# cheese_cave.net
KiCad netlist of a schematic drawn in Altium Designer
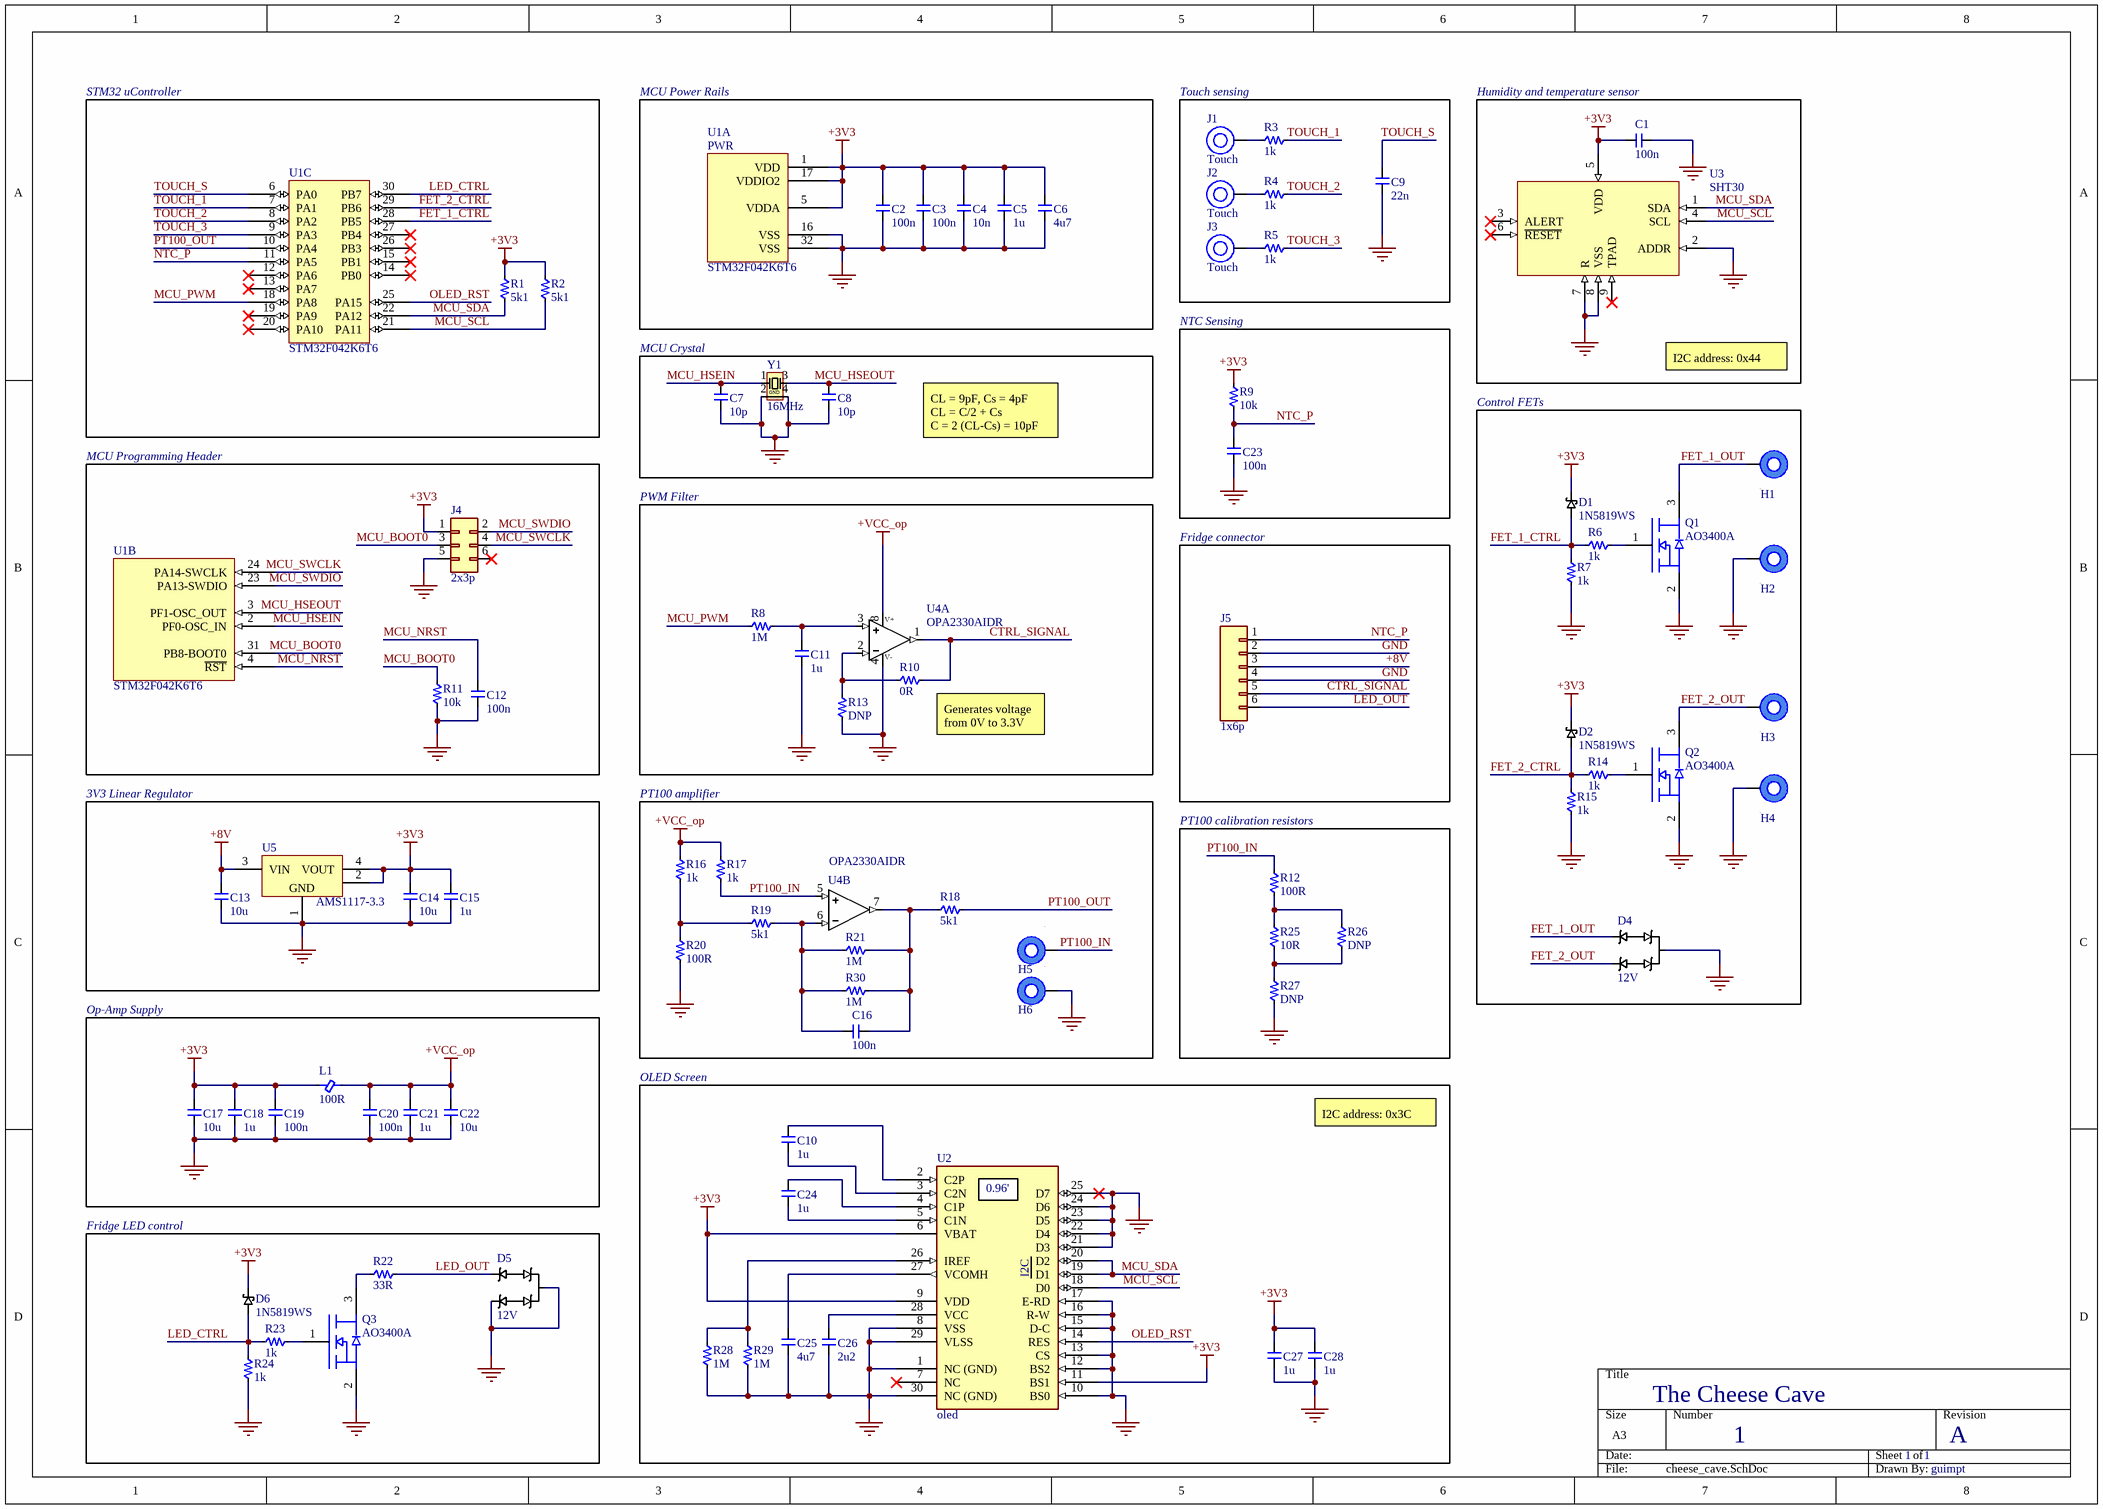
[diagram p0: cheese_cave.SchDoc]

(export (version "E")
  (design (tool "Eeschema 10.0.6"))
  (components
    (comp (ref "C1")
      (value "100n")
      (footprint "C0402")
      (description "0402 cap")
      (libsource (lib "FOC_Drive") (part "C_0402"))
    )
    (comp (ref "C2")
      (value "100n")
      (footprint "C0402")
      (description "0402 cap")
      (libsource (lib "FOC_Drive") (part "C_0402"))
    )
    (comp (ref "C3")
      (value "100n")
      (footprint "C0402")
      (description "0402 cap")
      (libsource (lib "FOC_Drive") (part "C_0402"))
    )
    (comp (ref "C4")
      (value "10n")
      (footprint "C0402")
      (description "0402 cap")
      (libsource (lib "cheese_cave") (part "C_0402"))
    )
    (comp (ref "C5")
      (value "1u")
      (footprint "C0805")
      (description "0805 cap")
      (libsource (lib "cheese_cave") (part "C_0805"))
    )
    (comp (ref "C6")
      (value "4u7")
      (footprint "C0805")
      (description "0805 cap")
      (libsource (lib "cheese_cave") (part "C_0805"))
    )
    (comp (ref "C7")
      (value "10p")
      (footprint "C0402")
      (description "0402 cap")
      (libsource (lib "FOC_Drive") (part "C_0402"))
    )
    (comp (ref "C8")
      (value "10p")
      (footprint "C0402")
      (description "0402 cap")
      (libsource (lib "FOC_Drive") (part "C_0402"))
    )
    (comp (ref "C9")
      (value "22n")
      (footprint "C0402")
      (description "0402 cap")
      (libsource (lib "FOC_Drive") (part "C_0402"))
    )
    (comp (ref "C10")
      (value "1u")
      (footprint "C0805")
      (description "0805 cap")
      (libsource (lib "cheese_cave") (part "C_0805"))
    )
    (comp (ref "C11")
      (value "1u")
      (footprint "C0805")
      (description "0805 cap")
      (libsource (lib "cheese_cave") (part "C_0805"))
    )
    (comp (ref "C12")
      (value "100n")
      (footprint "C0402")
      (description "0402 cap")
      (libsource (lib "FOC_Drive") (part "C_0402"))
    )
    (comp (ref "C13")
      (value "10u")
      (footprint "C0805")
      (description "0805 cap")
      (libsource (lib "FOC_Drive") (part "C_0805"))
    )
    (comp (ref "C14")
      (value "10u")
      (footprint "C0805")
      (description "0805 cap")
      (libsource (lib "FOC_Drive") (part "C_0805"))
    )
    (comp (ref "C15")
      (value "1u")
      (footprint "C0805")
      (description "0805 cap")
      (libsource (lib "cheese_cave") (part "C_0805"))
    )
    (comp (ref "C16")
      (value "100n")
      (footprint "C0402")
      (description "0402 cap")
      (libsource (lib "FOC_Drive") (part "C_0402"))
    )
    (comp (ref "C17")
      (value "10u")
      (footprint "C0805")
      (description "0805 cap")
      (libsource (lib "FOC_Drive") (part "C_0805"))
    )
    (comp (ref "C18")
      (value "1u")
      (footprint "C0805")
      (description "0805 cap")
      (libsource (lib "cheese_cave") (part "C_0805"))
    )
    (comp (ref "C19")
      (value "100n")
      (footprint "C0402")
      (description "0402 cap")
      (libsource (lib "FOC_Drive") (part "C_0402"))
    )
    (comp (ref "C20")
      (value "100n")
      (footprint "C0402")
      (description "0402 cap")
      (libsource (lib "FOC_Drive") (part "C_0402"))
    )
    (comp (ref "C21")
      (value "1u")
      (footprint "C0805")
      (description "0805 cap")
      (libsource (lib "cheese_cave") (part "C_0805"))
    )
    (comp (ref "C22")
      (value "10u")
      (footprint "C0805")
      (description "0805 cap")
      (libsource (lib "FOC_Drive") (part "C_0805"))
    )
    (comp (ref "C23")
      (value "100n")
      (footprint "C0402")
      (description "0402 cap")
      (libsource (lib "FOC_Drive") (part "C_0402"))
    )
    (comp (ref "C24")
      (value "1u")
      (footprint "C0805")
      (description "0805 cap")
      (libsource (lib "cheese_cave") (part "C_0805"))
    )
    (comp (ref "C25")
      (value "4u7")
      (footprint "C0805")
      (description "0805 cap")
      (libsource (lib "cheese_cave") (part "C_0805"))
    )
    (comp (ref "C26")
      (value "2u2")
      (footprint "C0805")
      (description "0805 cap")
      (libsource (lib "FOC_Drive") (part "C_0805"))
    )
    (comp (ref "C27")
      (value "1u")
      (footprint "C0805")
      (description "0805 cap")
      (libsource (lib "cheese_cave") (part "C_0805"))
    )
    (comp (ref "C28")
      (value "1u")
      (footprint "C0805")
      (description "0805 cap")
      (libsource (lib "cheese_cave") (part "C_0805"))
    )
    (comp (ref "D1")
      (value "1N5819WS")
      (footprint "SOD323")
      (description "40V 600mV@1A 1A SOD-323  Schottky")
      (libsource (lib "cheese_cave") (part "1N5819WS"))
    )
    (comp (ref "D2")
      (value "1N5819WS")
      (footprint "SOD323")
      (description "40V 600mV@1A 1A SOD-323  Schottky")
      (libsource (lib "cheese_cave") (part "1N5819WS"))
    )
    (comp (ref "D4")
      (value "12V")
      (footprint "SOT23_protek")
      (description "19V 13.3V 12V SOT-23(TO-236)  TVS")
      (libsource (lib "cheese_cave") (part "PSM712-LF-T7"))
    )
    (comp (ref "D5")
      (value "12V")
      (footprint "SOT23_protek")
      (description "19V 13.3V 12V SOT-23(TO-236)  TVS")
      (libsource (lib "cheese_cave") (part "PSM712-LF-T7"))
    )
    (comp (ref "D6")
      (value "1N5819WS")
      (footprint "SOD323")
      (description "40V 600mV@1A 1A SOD-323  Schottky")
      (libsource (lib "cheese_cave") (part "1N5819WS"))
    )
    (comp (ref "H1")
      (value "1x1")
      (footprint "1x1p")
      (description "0.85mm hole")
      (libsource (lib "cheese_cave") (part "1x1p"))
    )
    (comp (ref "H2")
      (value "1x1")
      (footprint "1x1p")
      (description "0.85mm hole")
      (libsource (lib "cheese_cave") (part "1x1p"))
    )
    (comp (ref "H3")
      (value "1x1")
      (footprint "1x1p")
      (description "0.85mm hole")
      (libsource (lib "cheese_cave") (part "1x1p"))
    )
    (comp (ref "H4")
      (value "1x1")
      (footprint "1x1p")
      (description "0.85mm hole")
      (libsource (lib "cheese_cave") (part "1x1p"))
    )
    (comp (ref "H5")
      (value "1x1")
      (footprint "1x1p")
      (description "0.85mm hole")
      (libsource (lib "cheese_cave") (part "1x1p"))
    )
    (comp (ref "H6")
      (value "1x1")
      (footprint "1x1p")
      (description "0.85mm hole")
      (libsource (lib "cheese_cave") (part "1x1p"))
    )
    (comp (ref "J1")
      (value "Touch")
      (footprint "F10-10-6.5-0.4 Z")
      (libsource (lib "cheese_cave") (part "F10-10-6.5-0.4Z"))
    )
    (comp (ref "J2")
      (value "Touch")
      (footprint "F10-10-6.5-0.4 Z")
      (libsource (lib "cheese_cave") (part "F10-10-6.5-0.4Z"))
    )
    (comp (ref "J3")
      (value "Touch")
      (footprint "F10-10-6.5-0.4 Z")
      (libsource (lib "cheese_cave") (part "F10-10-6.5-0.4Z"))
    )
    (comp (ref "J4")
      (value "2x3p")
      (footprint "2x3p_conn")
      (description "2x3 male pin header")
      (libsource (lib "FOC_Drive") (part "2x3p_conn"))
    )
    (comp (ref "J5")
      (value "1x6p")
      (footprint "1X6P_CONN")
      (description "1x6 male pin header")
      (libsource (lib "cheese_cave") (part "1x6p_conn"))
    )
    (comp (ref "L1")
      (value "100R")
      (footprint "L0805")
      (description "±25% 100Ω@100MHz 0805  150mR Ferrite Beads")
      (libsource (lib "cheese_cave") (part "GZ2012D101TF"))
    )
    (comp (ref "Q1")
      (value "AO3400A")
      (footprint "SOT23_alphaomega")
      (description "30V 5.7A 26.5mΩ@10V,5.7A 1.4W N Channel SOT-23-3L  MOSFET")
      (libsource (lib "cheese_cave") (part "AO3400A"))
    )
    (comp (ref "Q2")
      (value "AO3400A")
      (footprint "SOT23_alphaomega")
      (description "30V 5.7A 26.5mΩ@10V,5.7A 1.4W N Channel SOT-23-3L  MOSFET")
      (libsource (lib "cheese_cave") (part "AO3400A"))
    )
    (comp (ref "Q3")
      (value "AO3400A")
      (footprint "SOT23_alphaomega")
      (description "30V 5.7A 26.5mΩ@10V,5.7A 1.4W N Channel SOT-23-3L  MOSFET")
      (libsource (lib "cheese_cave") (part "AO3400A"))
    )
    (comp (ref "R1")
      (value "5k1")
      (footprint "R0402")
      (description "0402 62.5mW")
      (libsource (lib "FOC_Drive") (part "R_0402"))
    )
    (comp (ref "R2")
      (value "5k1")
      (footprint "R0402")
      (description "0402 62.5mW")
      (libsource (lib "FOC_Drive") (part "R_0402"))
    )
    (comp (ref "R3")
      (value "1k")
      (footprint "R0402")
      (description "0402 62.5mW")
      (libsource (lib "FOC_Drive") (part "R_0402"))
    )
    (comp (ref "R4")
      (value "1k")
      (footprint "R0402")
      (description "0402 62.5mW")
      (libsource (lib "FOC_Drive") (part "R_0402"))
    )
    (comp (ref "R5")
      (value "1k")
      (footprint "R0402")
      (description "0402 62.5mW")
      (libsource (lib "FOC_Drive") (part "R_0402"))
    )
    (comp (ref "R6")
      (value "1k")
      (footprint "R0402")
      (description "0402 62.5mW")
      (libsource (lib "FOC_Drive") (part "R_0402"))
    )
    (comp (ref "R7")
      (value "1k")
      (footprint "R0402")
      (description "0402 62.5mW")
      (libsource (lib "FOC_Drive") (part "R_0402"))
    )
    (comp (ref "R8")
      (value "1M")
      (footprint "R0402")
      (description "0402 62.5mW")
      (libsource (lib "FOC_Drive") (part "R_0402"))
    )
    (comp (ref "R9")
      (value "10k")
      (footprint "R0402")
      (description "0402 62.5mW")
      (libsource (lib "FOC_Drive") (part "R_0402"))
    )
    (comp (ref "R10")
      (value "0R")
      (footprint "R0402")
      (description "0402 62.5mW")
      (libsource (lib "FOC_Drive") (part "R_0402"))
    )
    (comp (ref "R11")
      (value "10k")
      (footprint "R0402")
      (description "0402 62.5mW")
      (libsource (lib "FOC_Drive") (part "R_0402"))
    )
    (comp (ref "R12")
      (value "100R")
      (footprint "R0402")
      (description "0402 62.5mW")
      (libsource (lib "FOC_Drive") (part "R_0402"))
    )
    (comp (ref "R13")
      (value "DNP")
      (footprint "R0402")
      (description "0402 62.5mW")
      (libsource (lib "FOC_Drive") (part "R_0402"))
    )
    (comp (ref "R14")
      (value "1k")
      (footprint "R0402")
      (description "0402 62.5mW")
      (libsource (lib "FOC_Drive") (part "R_0402"))
    )
    (comp (ref "R15")
      (value "1k")
      (footprint "R0402")
      (description "0402 62.5mW")
      (libsource (lib "FOC_Drive") (part "R_0402"))
    )
    (comp (ref "R16")
      (value "1k")
      (footprint "R0402")
      (description "0402 62.5mW")
      (libsource (lib "FOC_Drive") (part "R_0402"))
    )
    (comp (ref "R17")
      (value "1k")
      (footprint "R0402")
      (description "0402 62.5mW")
      (libsource (lib "FOC_Drive") (part "R_0402"))
    )
    (comp (ref "R18")
      (value "5k1")
      (footprint "R0402")
      (description "0402 62.5mW")
      (libsource (lib "FOC_Drive") (part "R_0402"))
    )
    (comp (ref "R19")
      (value "5k1")
      (footprint "R0402")
      (description "0402 62.5mW")
      (libsource (lib "FOC_Drive") (part "R_0402"))
    )
    (comp (ref "R20")
      (value "100R")
      (footprint "R0402")
      (description "0402 62.5mW")
      (libsource (lib "FOC_Drive") (part "R_0402"))
    )
    (comp (ref "R21")
      (value "1M")
      (footprint "R0402")
      (description "0402 62.5mW")
      (libsource (lib "FOC_Drive") (part "R_0402"))
    )
    (comp (ref "R22")
      (value "33R")
      (footprint "R0402")
      (description "0402 62.5mW")
      (libsource (lib "FOC_Drive") (part "R_0402"))
    )
    (comp (ref "R23")
      (value "1k")
      (footprint "R0402")
      (description "0402 62.5mW")
      (libsource (lib "FOC_Drive") (part "R_0402"))
    )
    (comp (ref "R24")
      (value "1k")
      (footprint "R0402")
      (description "0402 62.5mW")
      (libsource (lib "FOC_Drive") (part "R_0402"))
    )
    (comp (ref "R25")
      (value "10R")
      (footprint "R0402")
      (description "0402 62.5mW")
      (libsource (lib "FOC_Drive") (part "R_0402"))
    )
    (comp (ref "R26")
      (value "DNP")
      (footprint "R0402")
      (description "0402 62.5mW")
      (libsource (lib "FOC_Drive") (part "R_0402"))
    )
    (comp (ref "R27")
      (value "DNP")
      (footprint "R0402")
      (description "0402 62.5mW")
      (libsource (lib "FOC_Drive") (part "R_0402"))
    )
    (comp (ref "R28")
      (value "1M")
      (footprint "R0402")
      (description "0402 62.5mW")
      (libsource (lib "FOC_Drive") (part "R_0402"))
    )
    (comp (ref "R29")
      (value "1M")
      (footprint "R0402")
      (description "0402 62.5mW")
      (libsource (lib "FOC_Drive") (part "R_0402"))
    )
    (comp (ref "R30")
      (value "1M")
      (footprint "R0402")
      (description "0402 62.5mW")
      (libsource (lib "FOC_Drive") (part "R_0402"))
    )
    (comp (ref "U1")
      (value "STM32F042K6T6")
      (footprint "LQFP32-ST")
      (description "RISC Microcontroller, 32-Bit, FLASH, CORTEX-M0 CPU, 48MHz, CMOS, PQFP32")
      (fields (field (name "MANUFACTURER") "STMicroelectronics"))
      (libsource (lib "cheese_cave") (part "STM32F042K6T6"))
    )
    (comp (ref "U2")
      (value "oled")
      (footprint "OLED_096_SSD1306")
      (description "0.96 inch frameless SSD1306 oled")
      (libsource (lib "cheese_cave") (part "OLED_096_SSD1306"))
    )
    (comp (ref "U3")
      (value "SHT30")
      (footprint "SHT30-DIS-B2.5KS")
      (description "Temperature and Humidity Sensor")
      (libsource (lib "cheese_cave") (part "SHT30-DIS-B2.5KS"))
    )
    (comp (ref "U4")
      (value "OPA2330AIDR")
      (footprint "SOIC8")
      (description "Precision opamp")
      (libsource (lib "cheese_cave") (part "OPA2330AIDR"))
    )
    (comp (ref "U5")
      (value "AMS1117-3.3")
      (footprint "SOT223")
      (description "72dB@(120Hz) 1A 1.3V@(800mA) Fixed 3.3V~3.3V Positive 1 SOT-223")
      (libsource (lib "FOC_Drive") (part "AMS1117-3.3"))
    )
    (comp (ref "Y1")
      (value "16MHz")
      (footprint "SMD3225-4P")
      (description "16MHz SMD Crystal Resonator 9pF ±10ppm ±30ppm -40℃~+85℃ SMD3225-4P Crystals ROHS")
      (libsource (lib "FOC_Drive") (part "X322516MLB4SI"))
    )
  )
  (nets
    (net (code "1") (name "+3V3") (class "Default")
      (node (ref "C1") (pin "1") (pinfunction "1_1") (pintype "passive"))
      (node (ref "C14") (pin "2") (pinfunction "2_2") (pintype "passive"))
      (node (ref "C15") (pin "2") (pinfunction "2_2") (pintype "passive"))
      (node (ref "C17") (pin "2") (pinfunction "2_2") (pintype "passive"))
      (node (ref "C18") (pin "2") (pinfunction "2_2") (pintype "passive"))
      (node (ref "C19") (pin "2") (pinfunction "2_2") (pintype "passive"))
      (node (ref "C2") (pin "2") (pinfunction "2_2") (pintype "passive"))
      (node (ref "C27") (pin "1") (pinfunction "1_1") (pintype "passive"))
      (node (ref "C28") (pin "1") (pinfunction "1_1") (pintype "passive"))
      (node (ref "C3") (pin "2") (pinfunction "2_2") (pintype "passive"))
      (node (ref "C4") (pin "2") (pinfunction "2_2") (pintype "passive"))
      (node (ref "C5") (pin "2") (pinfunction "2_2") (pintype "passive"))
      (node (ref "C6") (pin "2") (pinfunction "2_2") (pintype "passive"))
      (node (ref "D1") (pin "2") (pinfunction "2_2") (pintype "passive"))
      (node (ref "D2") (pin "2") (pinfunction "2_2") (pintype "passive"))
      (node (ref "D6") (pin "2") (pinfunction "2_2") (pintype "passive"))
      (node (ref "J4") (pin "1") (pinfunction "1_1") (pintype "passive"))
      (node (ref "L1") (pin "1") (pinfunction "1_1") (pintype "passive"))
      (node (ref "R1") (pin "1") (pinfunction "1_1") (pintype "passive"))
      (node (ref "R2") (pin "1") (pinfunction "1_1") (pintype "passive"))
      (node (ref "R9") (pin "2") (pinfunction "2_2") (pintype "passive"))
      (node (ref "U1") (pin "1") (pinfunction "VDD_1") (pintype "power_in"))
      (node (ref "U1") (pin "17") (pinfunction "VDDIO2_17") (pintype "power_in"))
      (node (ref "U1") (pin "5") (pinfunction "VDDA_5") (pintype "power_in"))
      (node (ref "U2") (pin "11") (pinfunction "BS1_11") (pintype "input"))
      (node (ref "U2") (pin "6") (pinfunction "VBAT_6") (pintype "power_in"))
      (node (ref "U2") (pin "9") (pinfunction "VDD_9") (pintype "power_in"))
      (node (ref "U3") (pin "5") (pinfunction "VDD_5") (pintype "input"))
      (node (ref "U5") (pin "2") (pinfunction "VOUT_2") (pintype "passive"))
      (node (ref "U5") (pin "4") (pinfunction "VOUT_4") (pintype "passive"))
    )
    (net (code "2") (name "+8V") (class "Default")
      (node (ref "C13") (pin "2") (pinfunction "2_2") (pintype "passive"))
      (node (ref "J5") (pin "3") (pinfunction "3_3") (pintype "passive"))
      (node (ref "U5") (pin "3") (pinfunction "VIN_3") (pintype "passive"))
    )
    (net (code "3") (name "+VCC_op") (class "Default")
      (node (ref "C20") (pin "2") (pinfunction "2_2") (pintype "passive"))
      (node (ref "C21") (pin "2") (pinfunction "2_2") (pintype "passive"))
      (node (ref "C22") (pin "2") (pinfunction "2_2") (pintype "passive"))
      (node (ref "L1") (pin "2") (pinfunction "2_2") (pintype "passive"))
      (node (ref "R16") (pin "2") (pinfunction "2_2") (pintype "passive"))
      (node (ref "R17") (pin "2") (pinfunction "2_2") (pintype "passive"))
      (node (ref "U4") (pin "8") (pinfunction "V+_8") (pintype "power_in"))
    )
    (net (code "4") (name "/CTRL_SIGNAL") (class "Default")
      (node (ref "J5") (pin "5") (pinfunction "5_5") (pintype "passive"))
      (node (ref "R10") (pin "2") (pinfunction "2_2") (pintype "passive"))
      (node (ref "U4") (pin "1") (pinfunction "outA_1") (pintype "output"))
    )
    (net (code "5") (name "/FET_1_CTRL") (class "Default")
      (node (ref "D1") (pin "1") (pinfunction "1_1") (pintype "passive"))
      (node (ref "R6") (pin "2") (pinfunction "2_2") (pintype "passive"))
      (node (ref "R7") (pin "2") (pinfunction "2_2") (pintype "passive"))
      (node (ref "U1") (pin "28") (pinfunction "PB5_28") (pintype "bidirectional"))
    )
    (net (code "6") (name "/FET_1_OUT") (class "Default")
      (node (ref "D4") (pin "1") (pinfunction "1_1") (pintype "passive"))
      (node (ref "H1") (pin "1") (pinfunction "1_1") (pintype "passive"))
      (node (ref "Q1") (pin "3") (pinfunction "3_3") (pintype "passive"))
    )
    (net (code "7") (name "/FET_2_CTRL") (class "Default")
      (node (ref "D2") (pin "1") (pinfunction "1_1") (pintype "passive"))
      (node (ref "R14") (pin "2") (pinfunction "2_2") (pintype "passive"))
      (node (ref "R15") (pin "2") (pinfunction "2_2") (pintype "passive"))
      (node (ref "U1") (pin "29") (pinfunction "PB6_29") (pintype "bidirectional"))
    )
    (net (code "8") (name "/FET_2_OUT") (class "Default")
      (node (ref "D4") (pin "2") (pinfunction "2_2") (pintype "passive"))
      (node (ref "H3") (pin "1") (pinfunction "1_1") (pintype "passive"))
      (node (ref "Q2") (pin "3") (pinfunction "3_3") (pintype "passive"))
    )
    (net (code "9") (name "/LED_CTRL") (class "Default")
      (node (ref "D6") (pin "1") (pinfunction "1_1") (pintype "passive"))
      (node (ref "R23") (pin "2") (pinfunction "2_2") (pintype "passive"))
      (node (ref "R24") (pin "2") (pinfunction "2_2") (pintype "passive"))
      (node (ref "U1") (pin "30") (pinfunction "PB7_30") (pintype "bidirectional"))
    )
    (net (code "10") (name "/LED_OUT") (class "Default")
      (node (ref "D5") (pin "1") (pinfunction "1_1") (pintype "passive"))
      (node (ref "J5") (pin "6") (pinfunction "6_6") (pintype "passive"))
      (node (ref "R22") (pin "2") (pinfunction "2_2") (pintype "passive"))
    )
    (net (code "11") (name "/MCU_BOOT0") (class "Default")
      (node (ref "J4") (pin "3") (pinfunction "3_3") (pintype "passive"))
      (node (ref "R11") (pin "2") (pinfunction "2_2") (pintype "passive"))
      (node (ref "U1") (pin "31") (pinfunction "PB8-BOOT0_31") (pintype "input"))
    )
    (net (code "12") (name "/MCU_HSEIN") (class "Default")
      (node (ref "C7") (pin "2") (pinfunction "2_2") (pintype "passive"))
      (node (ref "U1") (pin "2") (pinfunction "PF0-OSC_IN_2") (pintype "input"))
      (node (ref "Y1") (pin "1") (pinfunction "1_1") (pintype "passive"))
    )
    (net (code "13") (name "/MCU_HSEOUT") (class "Default")
      (node (ref "C8") (pin "2") (pinfunction "2_2") (pintype "passive"))
      (node (ref "U1") (pin "3") (pinfunction "PF1-OSC_OUT_3") (pintype "input"))
      (node (ref "Y1") (pin "3") (pinfunction "3_3") (pintype "passive"))
    )
    (net (code "14") (name "/MCU_NRST") (class "Default")
      (node (ref "C12") (pin "2") (pinfunction "2_2") (pintype "passive"))
      (node (ref "U1") (pin "4") (pinfunction "~{RST}_4") (pintype "input"))
    )
    (net (code "15") (name "/MCU_PWM") (class "Default")
      (node (ref "R8") (pin "2") (pinfunction "2_2") (pintype "passive"))
      (node (ref "U1") (pin "18") (pinfunction "PA8_18") (pintype "bidirectional"))
    )
    (net (code "16") (name "/MCU_SCL") (class "Default")
      (node (ref "R2") (pin "2") (pinfunction "2_2") (pintype "passive"))
      (node (ref "U1") (pin "21") (pinfunction "PA11_21") (pintype "bidirectional"))
      (node (ref "U2") (pin "18") (pinfunction "D0_18") (pintype "bidirectional"))
      (node (ref "U3") (pin "4") (pinfunction "SCL_4") (pintype "input"))
    )
    (net (code "17") (name "/MCU_SDA") (class "Default")
      (node (ref "R1") (pin "2") (pinfunction "2_2") (pintype "passive"))
      (node (ref "U1") (pin "22") (pinfunction "PA12_22") (pintype "bidirectional"))
      (node (ref "U2") (pin "19") (pinfunction "D1_19") (pintype "bidirectional"))
      (node (ref "U2") (pin "20") (pinfunction "D2_20") (pintype "bidirectional"))
      (node (ref "U3") (pin "1") (pinfunction "SDA_1") (pintype "input"))
    )
    (net (code "18") (name "/MCU_SWCLK") (class "Default")
      (node (ref "J4") (pin "4") (pinfunction "4_4") (pintype "passive"))
      (node (ref "U1") (pin "24") (pinfunction "PA14-SWCLK_24") (pintype "input"))
    )
    (net (code "19") (name "/MCU_SWDIO") (class "Default")
      (node (ref "J4") (pin "2") (pinfunction "2_2") (pintype "passive"))
      (node (ref "U1") (pin "23") (pinfunction "PA13-SWDIO_23") (pintype "input"))
    )
    (net (code "20") (name "/NTC_P") (class "Default")
      (node (ref "C23") (pin "2") (pinfunction "2_2") (pintype "passive"))
      (node (ref "J5") (pin "1") (pinfunction "1_1") (pintype "passive"))
      (node (ref "R9") (pin "1") (pinfunction "1_1") (pintype "passive"))
      (node (ref "U1") (pin "11") (pinfunction "PA5_11") (pintype "bidirectional"))
    )
    (net (code "21") (name "/OLED_RST") (class "Default")
      (node (ref "U1") (pin "25") (pinfunction "PA15_25") (pintype "bidirectional"))
      (node (ref "U2") (pin "14") (pinfunction "RES_14") (pintype "input"))
    )
    (net (code "22") (name "/PT100_IN") (class "Default")
      (node (ref "H5") (pin "1") (pinfunction "1_1") (pintype "passive"))
      (node (ref "R12") (pin "2") (pinfunction "2_2") (pintype "passive"))
      (node (ref "R17") (pin "1") (pinfunction "1_1") (pintype "passive"))
      (node (ref "U4") (pin "5") (pinfunction "INB+_5") (pintype "input"))
    )
    (net (code "23") (name "/PT100_OUT") (class "Default")
      (node (ref "R18") (pin "2") (pinfunction "2_2") (pintype "passive"))
      (node (ref "U1") (pin "10") (pinfunction "PA4_10") (pintype "bidirectional"))
    )
    (net (code "24") (name "/TOUCH_1") (class "Default")
      (node (ref "R3") (pin "1") (pinfunction "1_1") (pintype "passive"))
      (node (ref "U1") (pin "7") (pinfunction "PA1_7") (pintype "bidirectional"))
    )
    (net (code "25") (name "/TOUCH_2") (class "Default")
      (node (ref "R4") (pin "1") (pinfunction "1_1") (pintype "passive"))
      (node (ref "U1") (pin "8") (pinfunction "PA2_8") (pintype "bidirectional"))
    )
    (net (code "26") (name "/TOUCH_3") (class "Default")
      (node (ref "R5") (pin "1") (pinfunction "1_1") (pintype "passive"))
      (node (ref "U1") (pin "9") (pinfunction "PA3_9") (pintype "bidirectional"))
    )
    (net (code "27") (name "/TOUCH_S") (class "Default")
      (node (ref "C9") (pin "2") (pinfunction "2_2") (pintype "passive"))
      (node (ref "U1") (pin "6") (pinfunction "PA0_6") (pintype "bidirectional"))
    )
    (net (code "28") (name "GND") (class "Default")
      (node (ref "C1") (pin "2") (pinfunction "2_2") (pintype "passive"))
      (node (ref "C11") (pin "1") (pinfunction "1_1") (pintype "passive"))
      (node (ref "C12") (pin "1") (pinfunction "1_1") (pintype "passive"))
      (node (ref "C13") (pin "1") (pinfunction "1_1") (pintype "passive"))
      (node (ref "C14") (pin "1") (pinfunction "1_1") (pintype "passive"))
      (node (ref "C15") (pin "1") (pinfunction "1_1") (pintype "passive"))
      (node (ref "C17") (pin "1") (pinfunction "1_1") (pintype "passive"))
      (node (ref "C18") (pin "1") (pinfunction "1_1") (pintype "passive"))
      (node (ref "C19") (pin "1") (pinfunction "1_1") (pintype "passive"))
      (node (ref "C2") (pin "1") (pinfunction "1_1") (pintype "passive"))
      (node (ref "C20") (pin "1") (pinfunction "1_1") (pintype "passive"))
      (node (ref "C21") (pin "1") (pinfunction "1_1") (pintype "passive"))
      (node (ref "C22") (pin "1") (pinfunction "1_1") (pintype "passive"))
      (node (ref "C23") (pin "1") (pinfunction "1_1") (pintype "passive"))
      (node (ref "C25") (pin "2") (pinfunction "2_2") (pintype "passive"))
      (node (ref "C26") (pin "2") (pinfunction "2_2") (pintype "passive"))
      (node (ref "C27") (pin "2") (pinfunction "2_2") (pintype "passive"))
      (node (ref "C28") (pin "2") (pinfunction "2_2") (pintype "passive"))
      (node (ref "C3") (pin "1") (pinfunction "1_1") (pintype "passive"))
      (node (ref "C4") (pin "1") (pinfunction "1_1") (pintype "passive"))
      (node (ref "C5") (pin "1") (pinfunction "1_1") (pintype "passive"))
      (node (ref "C6") (pin "1") (pinfunction "1_1") (pintype "passive"))
      (node (ref "C7") (pin "1") (pinfunction "1_1") (pintype "passive"))
      (node (ref "C8") (pin "1") (pinfunction "1_1") (pintype "passive"))
      (node (ref "C9") (pin "1") (pinfunction "1_1") (pintype "passive"))
      (node (ref "D4") (pin "3") (pinfunction "3_3") (pintype "passive"))
      (node (ref "D5") (pin "2") (pinfunction "2_2") (pintype "passive"))
      (node (ref "D5") (pin "3") (pinfunction "3_3") (pintype "passive"))
      (node (ref "H2") (pin "1") (pinfunction "1_1") (pintype "passive"))
      (node (ref "H4") (pin "1") (pinfunction "1_1") (pintype "passive"))
      (node (ref "H6") (pin "1") (pinfunction "1_1") (pintype "passive"))
      (node (ref "J4") (pin "5") (pinfunction "5_5") (pintype "passive"))
      (node (ref "J5") (pin "2") (pinfunction "2_2") (pintype "passive"))
      (node (ref "J5") (pin "4") (pinfunction "4_4") (pintype "passive"))
      (node (ref "Q1") (pin "2") (pinfunction "2_2") (pintype "passive"))
      (node (ref "Q2") (pin "2") (pinfunction "2_2") (pintype "passive"))
      (node (ref "Q3") (pin "2") (pinfunction "2_2") (pintype "passive"))
      (node (ref "R11") (pin "1") (pinfunction "1_1") (pintype "passive"))
      (node (ref "R13") (pin "1") (pinfunction "1_1") (pintype "passive"))
      (node (ref "R15") (pin "1") (pinfunction "1_1") (pintype "passive"))
      (node (ref "R20") (pin "1") (pinfunction "1_1") (pintype "passive"))
      (node (ref "R24") (pin "1") (pinfunction "1_1") (pintype "passive"))
      (node (ref "R27") (pin "1") (pinfunction "1_1") (pintype "passive"))
      (node (ref "R28") (pin "1") (pinfunction "1_1") (pintype "passive"))
      (node (ref "R29") (pin "1") (pinfunction "1_1") (pintype "passive"))
      (node (ref "R7") (pin "1") (pinfunction "1_1") (pintype "passive"))
      (node (ref "U1") (pin "16") (pinfunction "VSS_16") (pintype "power_in"))
      (node (ref "U1") (pin "32") (pinfunction "VSS_32") (pintype "power_in"))
      (node (ref "U2") (pin "1") (pinfunction "NC_(GND)_1") (pintype "passive"))
      (node (ref "U2") (pin "10") (pinfunction "BS0_10") (pintype "input"))
      (node (ref "U2") (pin "12") (pinfunction "BS2_12") (pintype "input"))
      (node (ref "U2") (pin "13") (pinfunction "CS_13") (pintype "input"))
      (node (ref "U2") (pin "15") (pinfunction "D-C_15") (pintype "input"))
      (node (ref "U2") (pin "16") (pinfunction "R-W_16") (pintype "input"))
      (node (ref "U2") (pin "17") (pinfunction "E-RD_17") (pintype "input"))
      (node (ref "U2") (pin "21") (pinfunction "D3_21") (pintype "bidirectional"))
      (node (ref "U2") (pin "22") (pinfunction "D4_22") (pintype "bidirectional"))
      (node (ref "U2") (pin "23") (pinfunction "D5_23") (pintype "bidirectional"))
      (node (ref "U2") (pin "24") (pinfunction "D6_24") (pintype "bidirectional"))
      (node (ref "U2") (pin "25") (pinfunction "D7_25") (pintype "bidirectional"))
      (node (ref "U2") (pin "29") (pinfunction "VLSS_29") (pintype "power_in"))
      (node (ref "U2") (pin "30") (pinfunction "NC_(GND)_30") (pintype "passive"))
      (node (ref "U2") (pin "8") (pinfunction "VSS_8") (pintype "power_in"))
      (node (ref "U3") (pin "2") (pinfunction "ADDR_2") (pintype "input"))
      (node (ref "U3") (pin "7") (pinfunction "R_7") (pintype "input"))
      (node (ref "U3") (pin "8") (pinfunction "VSS_8") (pintype "input"))
      (node (ref "U4") (pin "4") (pinfunction "V-_4") (pintype "power_in"))
      (node (ref "U5") (pin "1") (pinfunction "GND_1") (pintype "passive"))
      (node (ref "Y1") (pin "2") (pinfunction "2_2") (pintype "passive"))
      (node (ref "Y1") (pin "4") (pinfunction "4_4") (pintype "passive"))
    )
    (net (code "29") (name "Net-(J1-Pad1)") (class "Default")
      (node (ref "J1") (pin "1") (pinfunction "1_1") (pintype "passive"))
      (node (ref "R3") (pin "2") (pinfunction "2_2") (pintype "passive"))
    )
    (net (code "30") (name "Net-(J2-Pad1)") (class "Default")
      (node (ref "J2") (pin "1") (pinfunction "1_1") (pintype "passive"))
      (node (ref "R4") (pin "2") (pinfunction "2_2") (pintype "passive"))
    )
    (net (code "31") (name "Net-(J3-Pad1)") (class "Default")
      (node (ref "J3") (pin "1") (pinfunction "1_1") (pintype "passive"))
      (node (ref "R5") (pin "2") (pinfunction "2_2") (pintype "passive"))
    )
    (net (code "32") (name "Net-(Q1-Pad1)") (class "Default")
      (node (ref "Q1") (pin "1") (pinfunction "1_1") (pintype "passive"))
      (node (ref "R6") (pin "1") (pinfunction "1_1") (pintype "passive"))
    )
    (net (code "33") (name "Net-(Q2-Pad1)") (class "Default")
      (node (ref "Q2") (pin "1") (pinfunction "1_1") (pintype "passive"))
      (node (ref "R14") (pin "1") (pinfunction "1_1") (pintype "passive"))
    )
    (net (code "34") (name "Net-(Q3-Pad1)") (class "Default")
      (node (ref "Q3") (pin "1") (pinfunction "1_1") (pintype "passive"))
      (node (ref "R23") (pin "1") (pinfunction "1_1") (pintype "passive"))
    )
    (net (code "35") (name "Net-(Q3-Pad3)") (class "Default")
      (node (ref "Q3") (pin "3") (pinfunction "3_3") (pintype "passive"))
      (node (ref "R22") (pin "1") (pinfunction "1_1") (pintype "passive"))
    )
    (net (code "36") (name "Net-(R12-Pad1)") (class "Default")
      (node (ref "R12") (pin "1") (pinfunction "1_1") (pintype "passive"))
      (node (ref "R25") (pin "2") (pinfunction "2_2") (pintype "passive"))
      (node (ref "R26") (pin "2") (pinfunction "2_2") (pintype "passive"))
    )
    (net (code "37") (name "Net-(R16-Pad1)") (class "Default")
      (node (ref "R16") (pin "1") (pinfunction "1_1") (pintype "passive"))
      (node (ref "R19") (pin "1") (pinfunction "1_1") (pintype "passive"))
      (node (ref "R20") (pin "2") (pinfunction "2_2") (pintype "passive"))
    )
    (net (code "38") (name "Net-(R25-Pad1)") (class "Default")
      (node (ref "R25") (pin "1") (pinfunction "1_1") (pintype "passive"))
      (node (ref "R26") (pin "1") (pinfunction "1_1") (pintype "passive"))
      (node (ref "R27") (pin "2") (pinfunction "2_2") (pintype "passive"))
    )
    (net (code "39") (name "Net-(U2-C1N)") (class "Default")
      (node (ref "C24") (pin "2") (pinfunction "2_2") (pintype "passive"))
      (node (ref "U2") (pin "5") (pinfunction "C1N_5") (pintype "input"))
    )
    (net (code "40") (name "Net-(U2-C1P)") (class "Default")
      (node (ref "C24") (pin "1") (pinfunction "1_1") (pintype "passive"))
      (node (ref "U2") (pin "4") (pinfunction "C1P_4") (pintype "input"))
    )
    (net (code "41") (name "Net-(U2-C2N)") (class "Default")
      (node (ref "C10") (pin "1") (pinfunction "1_1") (pintype "passive"))
      (node (ref "U2") (pin "3") (pinfunction "C2N_3") (pintype "input"))
    )
    (net (code "42") (name "Net-(U2-C2P)") (class "Default")
      (node (ref "C10") (pin "2") (pinfunction "2_2") (pintype "passive"))
      (node (ref "U2") (pin "2") (pinfunction "C2P_2") (pintype "input"))
    )
    (net (code "43") (name "Net-(U2-IREF)") (class "Default")
      (node (ref "R28") (pin "2") (pinfunction "2_2") (pintype "passive"))
      (node (ref "R29") (pin "2") (pinfunction "2_2") (pintype "passive"))
      (node (ref "U2") (pin "26") (pinfunction "IREF_26") (pintype "input"))
    )
    (net (code "44") (name "Net-(U2-VCC)") (class "Default")
      (node (ref "C26") (pin "1") (pinfunction "1_1") (pintype "passive"))
      (node (ref "U2") (pin "28") (pinfunction "VCC_28") (pintype "power_in"))
    )
    (net (code "45") (name "Net-(U2-VCOMH)") (class "Default")
      (node (ref "C25") (pin "1") (pinfunction "1_1") (pintype "passive"))
      (node (ref "U2") (pin "27") (pinfunction "VCOMH_27") (pintype "output"))
    )
    (net (code "46") (name "Net-(U4A-INA+)") (class "Default")
      (node (ref "C11") (pin "2") (pinfunction "2_2") (pintype "passive"))
      (node (ref "R8") (pin "1") (pinfunction "1_1") (pintype "passive"))
      (node (ref "U4") (pin "3") (pinfunction "INA+_3") (pintype "input"))
    )
    (net (code "47") (name "Net-(U4A-INA-)") (class "Default")
      (node (ref "R10") (pin "1") (pinfunction "1_1") (pintype "passive"))
      (node (ref "R13") (pin "2") (pinfunction "2_2") (pintype "passive"))
      (node (ref "U4") (pin "2") (pinfunction "INA-_2") (pintype "input"))
    )
    (net (code "48") (name "Net-(U4B-INB-)") (class "Default")
      (node (ref "C16") (pin "2") (pinfunction "2_2") (pintype "passive"))
      (node (ref "R19") (pin "2") (pinfunction "2_2") (pintype "passive"))
      (node (ref "R21") (pin "1") (pinfunction "1_1") (pintype "passive"))
      (node (ref "R30") (pin "1") (pinfunction "1_1") (pintype "passive"))
      (node (ref "U4") (pin "6") (pinfunction "INB-_6") (pintype "input"))
    )
    (net (code "49") (name "Net-(U4B-outB)") (class "Default")
      (node (ref "C16") (pin "1") (pinfunction "1_1") (pintype "passive"))
      (node (ref "R18") (pin "1") (pinfunction "1_1") (pintype "passive"))
      (node (ref "R21") (pin "2") (pinfunction "2_2") (pintype "passive"))
      (node (ref "R30") (pin "2") (pinfunction "2_2") (pintype "passive"))
      (node (ref "U4") (pin "7") (pinfunction "outB_7") (pintype "output"))
    )
    (net (code "50") (name "unconnected-(J4-Pad6)") (class "Default")
      (node (ref "J4") (pin "6") (pinfunction "6_6") (pintype "passive+no_connect"))
    )
    (net (code "51") (name "unconnected-(U1C-PA6-Pad12)") (class "Default")
      (node (ref "U1") (pin "12") (pinfunction "PA6_12") (pintype "bidirectional+no_connect"))
    )
    (net (code "52") (name "unconnected-(U1C-PA7-Pad13)") (class "Default")
      (node (ref "U1") (pin "13") (pinfunction "PA7_13") (pintype "bidirectional+no_connect"))
    )
    (net (code "53") (name "unconnected-(U1C-PA9-Pad19)") (class "Default")
      (node (ref "U1") (pin "19") (pinfunction "PA9_19") (pintype "bidirectional+no_connect"))
    )
    (net (code "54") (name "unconnected-(U1C-PA10-Pad20)") (class "Default")
      (node (ref "U1") (pin "20") (pinfunction "PA10_20") (pintype "bidirectional+no_connect"))
    )
    (net (code "55") (name "unconnected-(U1C-PB0-Pad14)") (class "Default")
      (node (ref "U1") (pin "14") (pinfunction "PB0_14") (pintype "bidirectional+no_connect"))
    )
    (net (code "56") (name "unconnected-(U1C-PB1-Pad15)") (class "Default")
      (node (ref "U1") (pin "15") (pinfunction "PB1_15") (pintype "bidirectional+no_connect"))
    )
    (net (code "57") (name "unconnected-(U1C-PB3-Pad26)") (class "Default")
      (node (ref "U1") (pin "26") (pinfunction "PB3_26") (pintype "bidirectional+no_connect"))
    )
    (net (code "58") (name "unconnected-(U1C-PB4-Pad27)") (class "Default")
      (node (ref "U1") (pin "27") (pinfunction "PB4_27") (pintype "bidirectional+no_connect"))
    )
    (net (code "59") (name "unconnected-(U2-NC-Pad7)") (class "Default")
      (node (ref "U2") (pin "7") (pinfunction "NC_7") (pintype "passive+no_connect"))
    )
    (net (code "60") (name "unconnected-(U3-ALERT-Pad3)") (class "Default")
      (node (ref "U3") (pin "3") (pinfunction "ALERT_3") (pintype "input+no_connect"))
    )
    (net (code "61") (name "unconnected-(U3-TPAD-Pad9)") (class "Default")
      (node (ref "U3") (pin "9") (pinfunction "TPAD_9") (pintype "input+no_connect"))
    )
    (net (code "62") (name "unconnected-(U3-~{RESET}-Pad6)") (class "Default")
      (node (ref "U3") (pin "6") (pinfunction "~{RESET}_6") (pintype "input+no_connect"))
    )
  )
)
